# miniAwtrix.net
KiCad netlist of a schematic drawn in Altium Designer
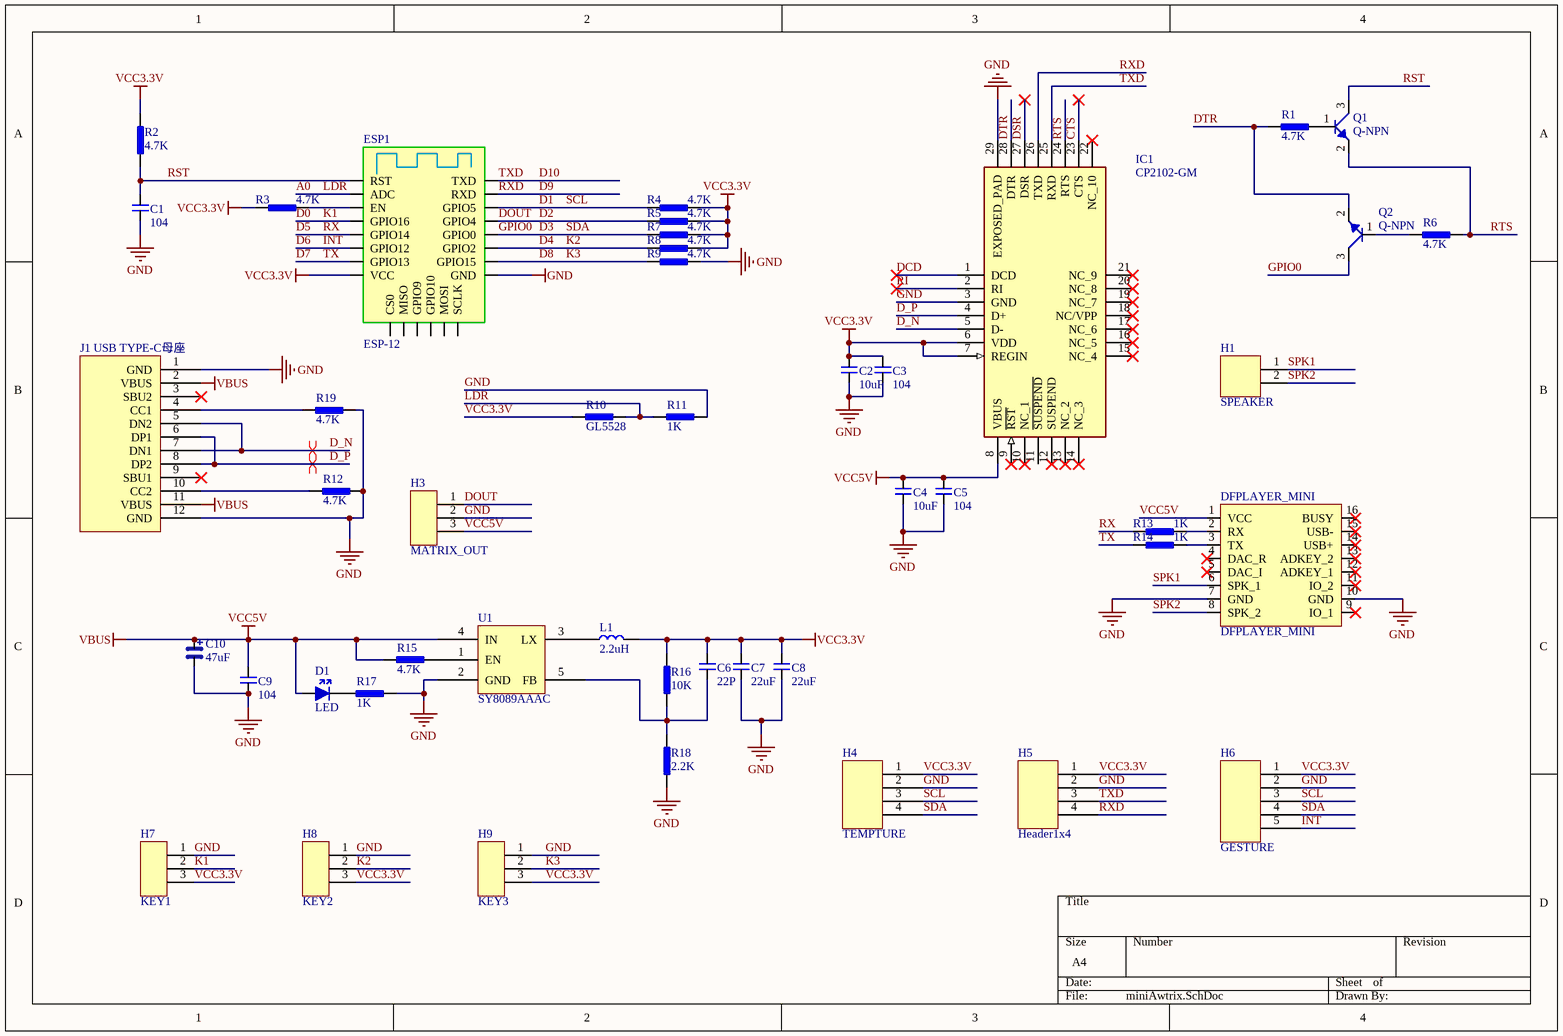
[diagram p0: miniAwtrix.SchDoc]

(export (version "E")
  (design (tool "Eeschema 10.0.6"))
  (components
    (comp (ref "C1")
      (value "104")
      (footprint "C0805")
      (description "Cap")
      (libsource (lib "SCH_Bacsic") (part "CAP"))
    )
    (comp (ref "C2")
      (value "10uF")
      (footprint "C0805")
      (description "Cap")
      (libsource (lib "SCH_Bacsic") (part "CAP"))
    )
    (comp (ref "C3")
      (value "104")
      (footprint "C0805")
      (description "Cap")
      (libsource (lib "SCH_Bacsic") (part "CAP"))
    )
    (comp (ref "C4")
      (value "10uF")
      (footprint "C0805")
      (description "Cap")
      (libsource (lib "SCH_Bacsic") (part "CAP"))
    )
    (comp (ref "C5")
      (value "104")
      (footprint "C0805")
      (description "Cap")
      (libsource (lib "SCH_Bacsic") (part "CAP"))
    )
    (comp (ref "C6")
      (value "22P")
      (footprint "C0805")
      (description "Cap")
      (libsource (lib "SCH_Bacsic") (part "CAP"))
    )
    (comp (ref "C7")
      (value "22uF")
      (footprint "C0805")
      (description "Cap")
      (libsource (lib "SCH_Bacsic") (part "CAP"))
    )
    (comp (ref "C8")
      (value "22uF")
      (footprint "C0805")
      (description "Cap")
      (libsource (lib "SCH_Bacsic") (part "CAP"))
    )
    (comp (ref "C9")
      (value "104")
      (footprint "C0805")
      (description "Cap")
      (libsource (lib "SCH_Bacsic") (part "CAP"))
    )
    (comp (ref "C10")
      (value "47uF")
      (footprint "TAN-3528")
      (description "钽电容")
      (libsource (lib "SCH_Bacsic") (part "C-TAN"))
    )
    (comp (ref "D1") (value "LED") (footprint "LED0805") (libsource (lib "SCH_Bacsic") (part "LED")))
    (comp (ref "DFPLAYER_MINI")
      (value "DFPLAYER_MINI")
      (footprint "DFPLAYER-MINI")
      (libsource (lib "Sch") (part "DFPLAYER_MINI"))
    )
    (comp (ref "ESP1")
      (value "ESP-12")
      (footprint "ESP12F - duplicate")
      (libsource (lib "SCH_Independent_Component") (part "ESP12F"))
    )
    (comp (ref "H1")
      (value "SPEAKER")
      (footprint "HDR1X2_2.54")
      (libsource (lib "SCH_Connector") (part "Header1x2"))
    )
    (comp (ref "H3")
      (value "MATRIX_OUT")
      (footprint "HDR1X3")
      (libsource (lib "SCH_Connector") (part "Header1x3"))
    )
    (comp (ref "H4")
      (value "TEMPTURE")
      (footprint "HDR1X4_2.54")
      (libsource (lib "SCH_Connector") (part "Header1x4"))
    )
    (comp (ref "H5")
      (value "Header1x4")
      (footprint "HDR1X4_2.54")
      (libsource (lib "SCH_Connector") (part "Header1x4"))
    )
    (comp (ref "H6")
      (value "GESTURE")
      (footprint "HDR1X5_2.54")
      (libsource (lib "SCH_Connector") (part "Header1x5"))
    )
    (comp (ref "H7")
      (value "KEY1")
      (footprint "HDR1X3_2.54")
      (libsource (lib "SCH_Connector") (part "Header1x3"))
    )
    (comp (ref "H8")
      (value "KEY2")
      (footprint "HDR1X3_2.54")
      (libsource (lib "SCH_Connector") (part "Header1x3"))
    )
    (comp (ref "H9")
      (value "KEY3")
      (footprint "HDR1X3_2.54")
      (libsource (lib "SCH_Connector") (part "Header1x3"))
    )
    (comp (ref "IC1")
      (value "CP2102-GM")
      (footprint "SamacSys:QFN50P500X500X100-29N-D")
      (description "Integrated Circuit")
      (fields (field (name "MOUSER PART NUMBER") "634-CP2102-GM") (field (name "RS PART NUMBER") "5268841"))
      (libsource (lib "*") (part "CP2102-GM"))
    )
    (comp (ref "J1")
      (value "USB TYPE-C母座")
      (footprint "USB-TYPEC-SMT")
      (libsource (lib "SCH_Connector") (part "USB TYPE-C"))
    )
    (comp (ref "L1")
      (value "2.2uH")
      (footprint "L-CDR5*5")
      (libsource (lib "SCH_Bacsic") (part "Inductance"))
    )
    (comp (ref "Q1") (value "Q-NPN") (footprint "SOT-23") (libsource (lib "SCH_Bacsic") (part "Q-NPN")))
    (comp (ref "Q2") (value "Q-NPN") (footprint "SOT-23") (libsource (lib "SCH_Bacsic") (part "Q-NPN")))
    (comp (ref "R1") (value "4.7K") (footprint "R0805") (libsource (lib "SCH_Bacsic") (part "RES")))
    (comp (ref "R2") (value "4.7K") (footprint "R0805") (libsource (lib "") (part "RES_1")))
    (comp (ref "R3") (value "4.7K") (footprint "R0805") (libsource (lib "SCH_Bacsic") (part "RES")))
    (comp (ref "R4") (value "4.7K") (footprint "R0805") (libsource (lib "SCH_Bacsic") (part "RES")))
    (comp (ref "R5") (value "4.7K") (footprint "R0805") (libsource (lib "SCH_Bacsic") (part "RES")))
    (comp (ref "R6") (value "4.7K") (footprint "R0805") (libsource (lib "SCH_Bacsic") (part "RES")))
    (comp (ref "R7") (value "4.7K") (footprint "R0805") (libsource (lib "SCH_Bacsic") (part "RES")))
    (comp (ref "R8") (value "4.7K") (footprint "R0805") (libsource (lib "SCH_Bacsic") (part "RES")))
    (comp (ref "R9") (value "4.7K") (footprint "R0805") (libsource (lib "SCH_Bacsic") (part "RES")))
    (comp (ref "R10") (value "GL5528") (footprint "HDR1X2_2.54") (libsource (lib "SCH_Bacsic") (part "RES")))
    (comp (ref "R11") (value "1K") (footprint "R0805") (libsource (lib "SCH_Bacsic") (part "RES")))
    (comp (ref "R12") (value "4.7K") (footprint "R0805") (libsource (lib "SCH_Bacsic") (part "RES")))
    (comp (ref "R13") (value "1K") (footprint "R0805") (libsource (lib "SCH_Bacsic") (part "RES")))
    (comp (ref "R14") (value "1K") (footprint "R0805") (libsource (lib "SCH_Bacsic") (part "RES")))
    (comp (ref "R15") (value "4.7K") (footprint "R0805") (libsource (lib "SCH_Bacsic") (part "RES")))
    (comp (ref "R16") (value "10K") (footprint "R0805") (libsource (lib "") (part "RES_1")))
    (comp (ref "R17") (value "1K") (footprint "R0805") (libsource (lib "SCH_Bacsic") (part "RES")))
    (comp (ref "R18") (value "2.2K") (footprint "R0805") (libsource (lib "") (part "RES_1")))
    (comp (ref "R19") (value "4.7K") (footprint "R0805") (libsource (lib "SCH_Bacsic") (part "RES")))
    (comp (ref "U1")
      (value "SY8089AAAC")
      (footprint "SOT-23-5")
      (libsource (lib "SCH_Integrated_Circuit") (part "SY8089AAAC"))
    )
  )
  (nets
    (net (code "1") (name "/A0") (class "Default")
      (node (ref "ESP1") (pin "2") (pinfunction "ADC_2") (pintype "passive"))
      (node (ref "R10") (pin "2") (pintype "passive"))
      (node (ref "R11") (pin "1") (pintype "passive"))
    )
    (net (code "2") (name "/CTS") (class "Default")
      (node (ref "IC1") (pin "23") (pinfunction "CTS_23") (pintype "passive+no_connect"))
    )
    (net (code "3") (name "/D0") (class "Default")
      (node (ref "ESP1") (pin "4") (pinfunction "GPIO16_4") (pintype "passive"))
      (node (ref "H7") (pin "2") (pintype "passive"))
    )
    (net (code "4") (name "/D1") (class "Default")
      (node (ref "ESP1") (pin "20") (pinfunction "GPIO5_20") (pintype "passive"))
      (node (ref "H4") (pin "3") (pintype "passive"))
      (node (ref "H6") (pin "3") (pintype "passive"))
      (node (ref "R4") (pin "1") (pintype "passive"))
    )
    (net (code "5") (name "/D2") (class "Default")
      (node (ref "ESP1") (pin "19") (pinfunction "GPIO4_19") (pintype "passive"))
      (node (ref "H3") (pin "1") (pintype "passive"))
      (node (ref "R5") (pin "1") (pintype "passive"))
    )
    (net (code "6") (name "/D3") (class "Default")
      (node (ref "ESP1") (pin "18") (pinfunction "GPIO0_18") (pintype "passive"))
      (node (ref "H4") (pin "4") (pintype "passive"))
      (node (ref "H6") (pin "4") (pintype "passive"))
      (node (ref "Q2") (pin "3") (pinfunction "3_3") (pintype "passive"))
      (node (ref "R7") (pin "1") (pintype "passive"))
    )
    (net (code "7") (name "/D4") (class "Default")
      (node (ref "ESP1") (pin "17") (pinfunction "GPIO2_17") (pintype "passive"))
      (node (ref "H8") (pin "2") (pintype "passive"))
      (node (ref "R8") (pin "1") (pintype "passive"))
    )
    (net (code "8") (name "/D5") (class "Default")
      (node (ref "ESP1") (pin "5") (pinfunction "GPIO14_5") (pintype "passive"))
      (node (ref "R13") (pin "1") (pintype "passive"))
    )
    (net (code "9") (name "/D6") (class "Default")
      (node (ref "ESP1") (pin "6") (pinfunction "GPIO12_6") (pintype "passive"))
      (node (ref "H6") (pin "5") (pintype "passive"))
    )
    (net (code "10") (name "/D7") (class "Default")
      (node (ref "ESP1") (pin "7") (pinfunction "GPIO13_7") (pintype "passive"))
      (node (ref "R14") (pin "1") (pintype "passive"))
    )
    (net (code "11") (name "/D8") (class "Default")
      (node (ref "ESP1") (pin "16") (pinfunction "GPIO15_16") (pintype "passive"))
      (node (ref "H9") (pin "2") (pintype "passive"))
      (node (ref "R9") (pin "1") (pintype "passive"))
    )
    (net (code "12") (name "/D9") (class "Default")
      (node (ref "ESP1") (pin "21") (pinfunction "RXD_21") (pintype "passive"))
      (node (ref "H5") (pin "4") (pintype "passive"))
      (node (ref "IC1") (pin "26") (pinfunction "TXD_26") (pintype "passive"))
    )
    (net (code "13") (name "/D10") (class "Default")
      (node (ref "ESP1") (pin "22") (pinfunction "TXD_22") (pintype "passive"))
      (node (ref "H5") (pin "3") (pintype "passive"))
      (node (ref "IC1") (pin "25") (pinfunction "RXD_25") (pintype "passive"))
    )
    (net (code "14") (name "/DCD") (class "Default")
      (node (ref "IC1") (pin "1") (pinfunction "DCD_1") (pintype "passive+no_connect"))
    )
    (net (code "15") (name "/DSR") (class "Default")
      (node (ref "IC1") (pin "27") (pinfunction "DSR_27") (pintype "passive+no_connect"))
    )
    (net (code "16") (name "/DTR") (class "Default")
      (node (ref "IC1") (pin "28") (pinfunction "DTR_28") (pintype "passive"))
      (node (ref "Q2") (pin "2") (pinfunction "2_2") (pintype "passive"))
      (node (ref "R1") (pin "1") (pintype "passive"))
    )
    (net (code "17") (name "/D_N") (class "Default")
      (node (ref "IC1") (pin "5") (pinfunction "D-_5") (pintype "passive"))
      (node (ref "J1") (pin "5") (pinfunction "DN2_5") (pintype "passive"))
      (node (ref "J1") (pin "7") (pinfunction "DN1_7") (pintype "passive"))
    )
    (net (code "18") (name "/D_P") (class "Default")
      (node (ref "IC1") (pin "4") (pinfunction "D+_4") (pintype "passive"))
      (node (ref "J1") (pin "6") (pinfunction "DP1_6") (pintype "passive"))
      (node (ref "J1") (pin "8") (pinfunction "DP2_8") (pintype "passive"))
    )
    (net (code "19") (name "/RI") (class "Default")
      (node (ref "IC1") (pin "2") (pinfunction "RI_2") (pintype "passive+no_connect"))
    )
    (net (code "20") (name "/RST") (class "Default")
      (node (ref "C1") (pin "2") (pintype "passive"))
      (node (ref "ESP1") (pin "1") (pinfunction "RST_1") (pintype "passive"))
      (node (ref "Q1") (pin "3") (pinfunction "3_3") (pintype "passive"))
      (node (ref "R2") (pin "1") (pintype "passive"))
    )
    (net (code "21") (name "/RTS") (class "Default")
      (node (ref "IC1") (pin "24") (pinfunction "RTS_24") (pintype "passive"))
      (node (ref "Q1") (pin "2") (pinfunction "2_2") (pintype "passive"))
      (node (ref "R6") (pin "2") (pintype "passive"))
    )
    (net (code "22") (name "/SPK1") (class "Default")
      (node (ref "DFPLAYER_MINI") (pin "6") (pinfunction "SPK_1_6") (pintype "passive"))
      (node (ref "H1") (pin "1") (pintype "passive"))
    )
    (net (code "23") (name "/SPK2") (class "Default")
      (node (ref "DFPLAYER_MINI") (pin "8") (pinfunction "SPK_2_8") (pintype "passive"))
      (node (ref "H1") (pin "2") (pintype "passive"))
    )
    (net (code "24") (name "GND") (class "Default")
      (node (ref "C1") (pin "1") (pintype "passive"))
      (node (ref "C10") (pin "2") (pintype "passive"))
      (node (ref "C2") (pin "1") (pintype "passive"))
      (node (ref "C3") (pin "1") (pintype "passive"))
      (node (ref "C4") (pin "1") (pintype "passive"))
      (node (ref "C5") (pin "1") (pintype "passive"))
      (node (ref "C7") (pin "1") (pintype "passive"))
      (node (ref "C8") (pin "1") (pintype "passive"))
      (node (ref "C9") (pin "1") (pintype "passive"))
      (node (ref "DFPLAYER_MINI") (pin "10") (pinfunction "GND_10") (pintype "passive"))
      (node (ref "DFPLAYER_MINI") (pin "7") (pinfunction "GND_7") (pintype "passive"))
      (node (ref "ESP1") (pin "15") (pinfunction "GND_15") (pintype "passive"))
      (node (ref "H3") (pin "2") (pintype "passive"))
      (node (ref "H4") (pin "2") (pintype "passive"))
      (node (ref "H5") (pin "2") (pintype "passive"))
      (node (ref "H6") (pin "2") (pintype "passive"))
      (node (ref "H7") (pin "1") (pintype "passive"))
      (node (ref "H8") (pin "1") (pintype "passive"))
      (node (ref "H9") (pin "1") (pintype "passive"))
      (node (ref "IC1") (pin "29") (pinfunction "EXPOSED_PAD_29") (pintype "passive"))
      (node (ref "IC1") (pin "3") (pinfunction "GND_3") (pintype "power_in"))
      (node (ref "J1") (pin "1") (pinfunction "GND_1") (pintype "passive"))
      (node (ref "J1") (pin "12") (pinfunction "GND_12") (pintype "passive"))
      (node (ref "R11") (pin "2") (pintype "passive"))
      (node (ref "R12") (pin "2") (pintype "passive"))
      (node (ref "R17") (pin "2") (pintype "passive"))
      (node (ref "R18") (pin "1") (pintype "passive"))
      (node (ref "R19") (pin "2") (pintype "passive"))
      (node (ref "R9") (pin "2") (pintype "passive"))
      (node (ref "U1") (pin "2") (pinfunction "GND_2") (pintype "passive"))
    )
    (net (code "25") (name "Net-(D1-Pad2)") (class "Default")
      (node (ref "D1") (pin "2") (pintype "passive"))
      (node (ref "R17") (pin "1") (pintype "passive"))
    )
    (net (code "26") (name "Net-(DFPLAYER_MINI-RX)") (class "Default")
      (node (ref "DFPLAYER_MINI") (pin "2") (pinfunction "RX_2") (pintype "passive"))
      (node (ref "R13") (pin "2") (pintype "passive"))
    )
    (net (code "27") (name "Net-(DFPLAYER_MINI-TX)") (class "Default")
      (node (ref "DFPLAYER_MINI") (pin "3") (pinfunction "TX_3") (pintype "passive"))
      (node (ref "R14") (pin "2") (pintype "passive"))
    )
    (net (code "28") (name "Net-(ESP1-EN)") (class "Default")
      (node (ref "ESP1") (pin "3") (pinfunction "EN_3") (pintype "passive"))
      (node (ref "R3") (pin "2") (pintype "passive"))
    )
    (net (code "29") (name "Net-(J1-CC1)") (class "Default")
      (node (ref "J1") (pin "4") (pinfunction "CC1_4") (pintype "passive"))
      (node (ref "R19") (pin "1") (pintype "passive"))
    )
    (net (code "30") (name "Net-(J1-CC2)") (class "Default")
      (node (ref "J1") (pin "10") (pinfunction "CC2_10") (pintype "passive"))
      (node (ref "R12") (pin "1") (pintype "passive"))
    )
    (net (code "31") (name "Net-(Q1-Pad1)") (class "Default")
      (node (ref "Q1") (pin "1") (pinfunction "1_1") (pintype "passive"))
      (node (ref "R1") (pin "2") (pintype "passive"))
    )
    (net (code "32") (name "Net-(Q2-Pad1)") (class "Default")
      (node (ref "Q2") (pin "1") (pinfunction "1_1") (pintype "passive"))
      (node (ref "R6") (pin "1") (pintype "passive"))
    )
    (net (code "33") (name "Net-(U1-EN)") (class "Default")
      (node (ref "R15") (pin "2") (pintype "passive"))
      (node (ref "U1") (pin "1") (pinfunction "EN_1") (pintype "passive"))
    )
    (net (code "34") (name "Net-(U1-FB)") (class "Default")
      (node (ref "C6") (pin "1") (pintype "passive"))
      (node (ref "R16") (pin "1") (pintype "passive"))
      (node (ref "R18") (pin "2") (pintype "passive"))
      (node (ref "U1") (pin "5") (pinfunction "FB_5") (pintype "passive"))
    )
    (net (code "35") (name "Net-(U1-LX)") (class "Default")
      (node (ref "L1") (pin "2") (pinfunction "2_2") (pintype "passive"))
      (node (ref "U1") (pin "3") (pinfunction "LX_3") (pintype "passive"))
    )
    (net (code "36") (name "VBUS") (class "Default")
      (node (ref "C10") (pin "1") (pintype "passive"))
      (node (ref "C4") (pin "2") (pintype "passive"))
      (node (ref "C5") (pin "2") (pintype "passive"))
      (node (ref "C9") (pin "2") (pintype "passive"))
      (node (ref "D1") (pin "1") (pintype "passive"))
      (node (ref "DFPLAYER_MINI") (pin "1") (pinfunction "VCC_1") (pintype "passive"))
      (node (ref "H3") (pin "3") (pintype "passive"))
      (node (ref "IC1") (pin "8") (pinfunction "VBUS_8") (pintype "passive"))
      (node (ref "J1") (pin "11") (pinfunction "VBUS_11") (pintype "passive"))
      (node (ref "J1") (pin "2") (pinfunction "VBUS_2") (pintype "passive"))
      (node (ref "R15") (pin "1") (pintype "passive"))
      (node (ref "U1") (pin "4") (pinfunction "IN_4") (pintype "passive"))
    )
    (net (code "37") (name "VCC3.3V") (class "Default")
      (node (ref "C2") (pin "2") (pintype "passive"))
      (node (ref "C3") (pin "2") (pintype "passive"))
      (node (ref "C6") (pin "2") (pintype "passive"))
      (node (ref "C7") (pin "2") (pintype "passive"))
      (node (ref "C8") (pin "2") (pintype "passive"))
      (node (ref "ESP1") (pin "8") (pinfunction "VCC_8") (pintype "passive"))
      (node (ref "H4") (pin "1") (pintype "passive"))
      (node (ref "H5") (pin "1") (pintype "passive"))
      (node (ref "H6") (pin "1") (pintype "passive"))
      (node (ref "H7") (pin "3") (pintype "passive"))
      (node (ref "H8") (pin "3") (pintype "passive"))
      (node (ref "H9") (pin "3") (pintype "passive"))
      (node (ref "IC1") (pin "6") (pinfunction "VDD_6") (pintype "power_in"))
      (node (ref "IC1") (pin "7") (pinfunction "REGIN_7") (pintype "input"))
      (node (ref "L1") (pin "1") (pinfunction "1_1") (pintype "passive"))
      (node (ref "R10") (pin "1") (pintype "passive"))
      (node (ref "R16") (pin "2") (pintype "passive"))
      (node (ref "R2") (pin "2") (pintype "passive"))
      (node (ref "R3") (pin "1") (pintype "passive"))
      (node (ref "R4") (pin "2") (pintype "passive"))
      (node (ref "R5") (pin "2") (pintype "passive"))
      (node (ref "R7") (pin "2") (pintype "passive"))
      (node (ref "R8") (pin "2") (pintype "passive"))
    )
    (net (code "38") (name "unconnected-(DFPLAYER_MINI-ADKEY_1-Pad12)") (class "Default")
      (node (ref "DFPLAYER_MINI") (pin "12") (pinfunction "ADKEY_1_12") (pintype "passive+no_connect"))
    )
    (net (code "39") (name "unconnected-(DFPLAYER_MINI-ADKEY_2-Pad13)") (class "Default")
      (node (ref "DFPLAYER_MINI") (pin "13") (pinfunction "ADKEY_2_13") (pintype "passive+no_connect"))
    )
    (net (code "40") (name "unconnected-(DFPLAYER_MINI-BUSY-Pad16)") (class "Default")
      (node (ref "DFPLAYER_MINI") (pin "16") (pinfunction "BUSY_16") (pintype "passive+no_connect"))
    )
    (net (code "41") (name "unconnected-(DFPLAYER_MINI-DAC_I-Pad5)") (class "Default")
      (node (ref "DFPLAYER_MINI") (pin "5") (pinfunction "DAC_I_5") (pintype "passive+no_connect"))
    )
    (net (code "42") (name "unconnected-(DFPLAYER_MINI-DAC_R-Pad4)") (class "Default")
      (node (ref "DFPLAYER_MINI") (pin "4") (pinfunction "DAC_R_4") (pintype "passive+no_connect"))
    )
    (net (code "43") (name "unconnected-(DFPLAYER_MINI-IO_1-Pad9)") (class "Default")
      (node (ref "DFPLAYER_MINI") (pin "9") (pinfunction "IO_1_9") (pintype "passive+no_connect"))
    )
    (net (code "44") (name "unconnected-(DFPLAYER_MINI-IO_2-Pad11)") (class "Default")
      (node (ref "DFPLAYER_MINI") (pin "11") (pinfunction "IO_2_11") (pintype "passive+no_connect"))
    )
    (net (code "45") (name "unconnected-(DFPLAYER_MINI-USB+-Pad14)") (class "Default")
      (node (ref "DFPLAYER_MINI") (pin "14") (pinfunction "USB+_14") (pintype "passive+no_connect"))
    )
    (net (code "46") (name "unconnected-(DFPLAYER_MINI-USB--Pad15)") (class "Default")
      (node (ref "DFPLAYER_MINI") (pin "15") (pinfunction "USB-_15") (pintype "passive+no_connect"))
    )
    (net (code "47") (name "unconnected-(ESP1-CS0-Pad9)") (class "Default")
      (node (ref "ESP1") (pin "9") (pinfunction "CS0_9") (pintype "passive"))
    )
    (net (code "48") (name "unconnected-(ESP1-GPIO9-Pad11)") (class "Default")
      (node (ref "ESP1") (pin "11") (pinfunction "GPIO9_11") (pintype "passive"))
    )
    (net (code "49") (name "unconnected-(ESP1-GPIO10-Pad12)") (class "Default")
      (node (ref "ESP1") (pin "12") (pinfunction "GPIO10_12") (pintype "passive"))
    )
    (net (code "50") (name "unconnected-(ESP1-MISO-Pad10)") (class "Default")
      (node (ref "ESP1") (pin "10") (pinfunction "MISO_10") (pintype "passive"))
    )
    (net (code "51") (name "unconnected-(ESP1-MOSI-Pad13)") (class "Default")
      (node (ref "ESP1") (pin "13") (pinfunction "MOSI_13") (pintype "passive"))
    )
    (net (code "52") (name "unconnected-(ESP1-SCLK-Pad14)") (class "Default")
      (node (ref "ESP1") (pin "14") (pinfunction "SCLK_14") (pintype "passive"))
    )
    (net (code "53") (name "unconnected-(IC1-NC_1-Pad10)") (class "Default")
      (node (ref "IC1") (pin "10") (pinfunction "NC_1_10") (pintype "passive+no_connect"))
    )
    (net (code "54") (name "unconnected-(IC1-NC_2-Pad13)") (class "Default")
      (node (ref "IC1") (pin "13") (pinfunction "NC_2_13") (pintype "passive+no_connect"))
    )
    (net (code "55") (name "unconnected-(IC1-NC_3-Pad14)") (class "Default")
      (node (ref "IC1") (pin "14") (pinfunction "NC_3_14") (pintype "passive+no_connect"))
    )
    (net (code "56") (name "unconnected-(IC1-NC_4-Pad15)") (class "Default")
      (node (ref "IC1") (pin "15") (pinfunction "NC_4_15") (pintype "passive+no_connect"))
    )
    (net (code "57") (name "unconnected-(IC1-NC_5-Pad16)") (class "Default")
      (node (ref "IC1") (pin "16") (pinfunction "NC_5_16") (pintype "passive+no_connect"))
    )
    (net (code "58") (name "unconnected-(IC1-NC_6-Pad17)") (class "Default")
      (node (ref "IC1") (pin "17") (pinfunction "NC_6_17") (pintype "passive+no_connect"))
    )
    (net (code "59") (name "unconnected-(IC1-NC_7-Pad19)") (class "Default")
      (node (ref "IC1") (pin "19") (pinfunction "NC_7_19") (pintype "passive+no_connect"))
    )
    (net (code "60") (name "unconnected-(IC1-NC_8-Pad20)") (class "Default")
      (node (ref "IC1") (pin "20") (pinfunction "NC_8_20") (pintype "passive+no_connect"))
    )
    (net (code "61") (name "unconnected-(IC1-NC_9-Pad21)") (class "Default")
      (node (ref "IC1") (pin "21") (pinfunction "NC_9_21") (pintype "passive+no_connect"))
    )
    (net (code "62") (name "unconnected-(IC1-NC_10-Pad22)") (class "Default")
      (node (ref "IC1") (pin "22") (pinfunction "NC_10_22") (pintype "passive+no_connect"))
    )
    (net (code "63") (name "unconnected-(IC1-NC{slash}VPP-Pad18)") (class "Default")
      (node (ref "IC1") (pin "18") (pinfunction "NC/VPP_18") (pintype "passive+no_connect"))
    )
    (net (code "64") (name "unconnected-(IC1-SUSPEND-Pad12)") (class "Default")
      (node (ref "IC1") (pin "12") (pinfunction "SUSPEND_12") (pintype "passive+no_connect"))
    )
    (net (code "65") (name "unconnected-(IC1-~{RST}-Pad9)") (class "Default")
      (node (ref "IC1") (pin "9") (pinfunction "~{RST}_9") (pintype "input+no_connect"))
    )
    (net (code "66") (name "unconnected-(IC1-~{SUSPEND}-Pad11)") (class "Default")
      (node (ref "IC1") (pin "11") (pinfunction "~{SUSPEND}_11") (pintype "passive"))
    )
    (net (code "67") (name "unconnected-(J1-SBU1-Pad9)") (class "Default")
      (node (ref "J1") (pin "9") (pinfunction "SBU1_9") (pintype "passive+no_connect"))
    )
    (net (code "68") (name "unconnected-(J1-SBU2-Pad3)") (class "Default")
      (node (ref "J1") (pin "3") (pinfunction "SBU2_3") (pintype "passive+no_connect"))
    )
  )
)
